# nixie_test.net
KiCad netlist of a schematic drawn in EAGLE
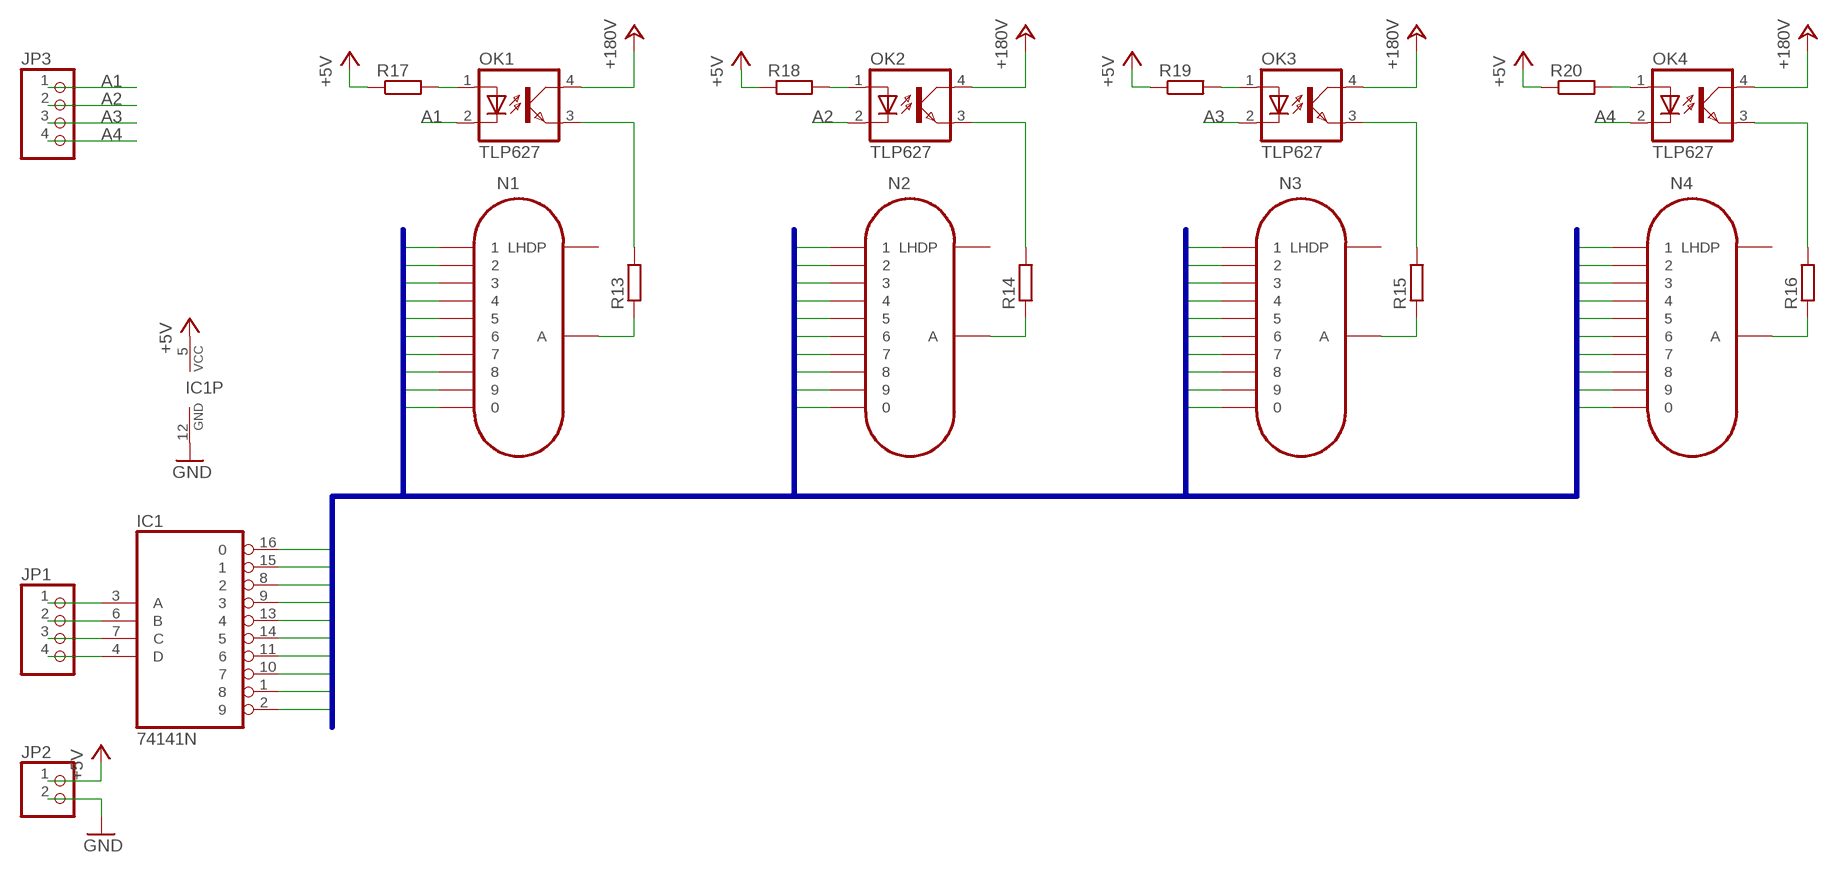
[diagram p0: schematic, sheet 1]

(export (version "E")
  (design (tool "Eeschema 10.0.6"))
  (components
    (comp (ref "IC1")
      (value "74141N")
      (footprint "eagle-import:DIL16")
      (libsource (lib "eagle-import") (part "74141N"))
    )
    (comp (ref "JP1")
      (value "PINHD-1X4")
      (footprint "eagle-import:1X04")
      (libsource (lib "eagle-import") (part "PINHD-1X4"))
    )
    (comp (ref "JP2")
      (value "PINHD-1X2")
      (footprint "eagle-import:1X02")
      (libsource (lib "eagle-import") (part "PINHD-1X2"))
    )
    (comp (ref "JP3")
      (value "PINHD-1X4")
      (footprint "eagle-import:1X04")
      (libsource (lib "eagle-import") (part "PINHD-1X4"))
    )
    (comp (ref "N1")
      (value "IN-12B")
      (footprint "eagle-import:IN-12")
      (libsource (lib "eagle-import") (part "IN-12B"))
    )
    (comp (ref "N2")
      (value "IN-12B")
      (footprint "eagle-import:IN-12")
      (libsource (lib "eagle-import") (part "IN-12B"))
    )
    (comp (ref "N3")
      (value "IN-12B")
      (footprint "eagle-import:IN-12")
      (libsource (lib "eagle-import") (part "IN-12B"))
    )
    (comp (ref "N4")
      (value "IN-12B")
      (footprint "eagle-import:IN-12")
      (libsource (lib "eagle-import") (part "IN-12B"))
    )
    (comp (ref "OK1")
      (value "TLP627")
      (footprint "eagle-import:4-SMD")
      (libsource (lib "eagle-import") (part "TLP627"))
    )
    (comp (ref "OK2")
      (value "TLP627")
      (footprint "eagle-import:4-SMD")
      (libsource (lib "eagle-import") (part "TLP627"))
    )
    (comp (ref "OK3")
      (value "TLP627")
      (footprint "eagle-import:4-SMD")
      (libsource (lib "eagle-import") (part "TLP627"))
    )
    (comp (ref "OK4")
      (value "TLP627")
      (footprint "eagle-import:4-SMD")
      (libsource (lib "eagle-import") (part "TLP627"))
    )
    (comp (ref "R13")
      (value "R-EU_10")
      (footprint "eagle-import:0207_10")
      (libsource (lib "eagle-import") (part "R-EU_10"))
    )
    (comp (ref "R14")
      (value "R-EU_10")
      (footprint "eagle-import:0207_10")
      (libsource (lib "eagle-import") (part "R-EU_10"))
    )
    (comp (ref "R15")
      (value "R-EU_10")
      (footprint "eagle-import:0207_10")
      (libsource (lib "eagle-import") (part "R-EU_10"))
    )
    (comp (ref "R16")
      (value "R-EU_10")
      (footprint "eagle-import:0207_10")
      (libsource (lib "eagle-import") (part "R-EU_10"))
    )
    (comp (ref "R17")
      (value "R-EU_10")
      (footprint "eagle-import:0207_10")
      (libsource (lib "eagle-import") (part "R-EU_10"))
    )
    (comp (ref "R18")
      (value "R-EU_10")
      (footprint "eagle-import:0207_10")
      (libsource (lib "eagle-import") (part "R-EU_10"))
    )
    (comp (ref "R19")
      (value "R-EU_10")
      (footprint "eagle-import:0207_10")
      (libsource (lib "eagle-import") (part "R-EU_10"))
    )
    (comp (ref "R20")
      (value "R-EU_10")
      (footprint "eagle-import:0207_10")
      (libsource (lib "eagle-import") (part "R-EU_10"))
    )
  )
  (nets
    (net (code "1") (name "+5V") (class "Default")
      (node (ref "IC1") (pin "5") (pinfunction "VCC_5") (pintype "power_in"))
      (node (ref "JP2") (pin "1") (pinfunction "1_1") (pintype "passive"))
      (node (ref "R17") (pin "1") (pinfunction "1_1") (pintype "passive"))
      (node (ref "R18") (pin "1") (pinfunction "1_1") (pintype "passive"))
      (node (ref "R19") (pin "1") (pinfunction "1_1") (pintype "passive"))
      (node (ref "R20") (pin "1") (pinfunction "1_1") (pintype "passive"))
    )
    (net (code "2") (name "+180V") (class "Default")
      (node (ref "OK1") (pin "4") (pinfunction "COL_4") (pintype "passive"))
      (node (ref "OK2") (pin "4") (pinfunction "COL_4") (pintype "passive"))
      (node (ref "OK3") (pin "4") (pinfunction "COL_4") (pintype "passive"))
      (node (ref "OK4") (pin "4") (pinfunction "COL_4") (pintype "passive"))
    )
    (net (code "3") (name "/A1") (class "Default")
      (node (ref "JP3") (pin "1") (pinfunction "1_1") (pintype "passive"))
      (node (ref "OK1") (pin "2") (pinfunction "C_2") (pintype "passive"))
    )
    (net (code "4") (name "/A2") (class "Default")
      (node (ref "JP3") (pin "2") (pinfunction "2_2") (pintype "passive"))
      (node (ref "OK2") (pin "2") (pinfunction "C_2") (pintype "passive"))
    )
    (net (code "5") (name "/A3") (class "Default")
      (node (ref "JP3") (pin "3") (pinfunction "3_3") (pintype "passive"))
      (node (ref "OK3") (pin "2") (pinfunction "C_2") (pintype "passive"))
    )
    (net (code "6") (name "/A4") (class "Default")
      (node (ref "JP3") (pin "4") (pinfunction "4_4") (pintype "passive"))
      (node (ref "OK4") (pin "2") (pinfunction "C_2") (pintype "passive"))
    )
    (net (code "7") (name "/C0") (class "Default")
      (node (ref "IC1") (pin "16") (pinfunction "0_16") (pintype "open_collector"))
      (node (ref "N1") (pin "0") (pinfunction "0_0") (pintype "bidirectional"))
      (node (ref "N2") (pin "0") (pinfunction "0_0") (pintype "bidirectional"))
      (node (ref "N3") (pin "0") (pinfunction "0_0") (pintype "bidirectional"))
      (node (ref "N4") (pin "0") (pinfunction "0_0") (pintype "bidirectional"))
    )
    (net (code "8") (name "/C1") (class "Default")
      (node (ref "IC1") (pin "15") (pinfunction "1_15") (pintype "open_collector"))
      (node (ref "N1") (pin "1") (pinfunction "1_1") (pintype "bidirectional"))
      (node (ref "N2") (pin "1") (pinfunction "1_1") (pintype "bidirectional"))
      (node (ref "N3") (pin "1") (pinfunction "1_1") (pintype "bidirectional"))
      (node (ref "N4") (pin "1") (pinfunction "1_1") (pintype "bidirectional"))
    )
    (net (code "9") (name "/C2") (class "Default")
      (node (ref "IC1") (pin "8") (pinfunction "2_8") (pintype "open_collector"))
      (node (ref "N1") (pin "2") (pinfunction "2_2") (pintype "bidirectional"))
      (node (ref "N2") (pin "2") (pinfunction "2_2") (pintype "bidirectional"))
      (node (ref "N3") (pin "2") (pinfunction "2_2") (pintype "bidirectional"))
      (node (ref "N4") (pin "2") (pinfunction "2_2") (pintype "bidirectional"))
    )
    (net (code "10") (name "/C3") (class "Default")
      (node (ref "IC1") (pin "9") (pinfunction "3_9") (pintype "open_collector"))
      (node (ref "N1") (pin "3") (pinfunction "3_3") (pintype "bidirectional"))
      (node (ref "N2") (pin "3") (pinfunction "3_3") (pintype "bidirectional"))
      (node (ref "N3") (pin "3") (pinfunction "3_3") (pintype "bidirectional"))
      (node (ref "N4") (pin "3") (pinfunction "3_3") (pintype "bidirectional"))
    )
    (net (code "11") (name "/C4") (class "Default")
      (node (ref "IC1") (pin "13") (pinfunction "4_13") (pintype "open_collector"))
      (node (ref "N1") (pin "4") (pinfunction "4_4") (pintype "bidirectional"))
      (node (ref "N2") (pin "4") (pinfunction "4_4") (pintype "bidirectional"))
      (node (ref "N3") (pin "4") (pinfunction "4_4") (pintype "bidirectional"))
      (node (ref "N4") (pin "4") (pinfunction "4_4") (pintype "bidirectional"))
    )
    (net (code "12") (name "/C5") (class "Default")
      (node (ref "IC1") (pin "14") (pinfunction "5_14") (pintype "open_collector"))
      (node (ref "N1") (pin "5") (pinfunction "5_5") (pintype "bidirectional"))
      (node (ref "N2") (pin "5") (pinfunction "5_5") (pintype "bidirectional"))
      (node (ref "N3") (pin "5") (pinfunction "5_5") (pintype "bidirectional"))
      (node (ref "N4") (pin "5") (pinfunction "5_5") (pintype "bidirectional"))
    )
    (net (code "13") (name "/C6") (class "Default")
      (node (ref "IC1") (pin "11") (pinfunction "6_11") (pintype "open_collector"))
      (node (ref "N1") (pin "6") (pinfunction "6_6") (pintype "bidirectional"))
      (node (ref "N2") (pin "6") (pinfunction "6_6") (pintype "bidirectional"))
      (node (ref "N3") (pin "6") (pinfunction "6_6") (pintype "bidirectional"))
      (node (ref "N4") (pin "6") (pinfunction "6_6") (pintype "bidirectional"))
    )
    (net (code "14") (name "/C7") (class "Default")
      (node (ref "IC1") (pin "10") (pinfunction "7_10") (pintype "open_collector"))
      (node (ref "N1") (pin "7") (pinfunction "7_7") (pintype "bidirectional"))
      (node (ref "N2") (pin "7") (pinfunction "7_7") (pintype "bidirectional"))
      (node (ref "N3") (pin "7") (pinfunction "7_7") (pintype "bidirectional"))
      (node (ref "N4") (pin "7") (pinfunction "7_7") (pintype "bidirectional"))
    )
    (net (code "15") (name "/C8") (class "Default")
      (node (ref "IC1") (pin "1") (pinfunction "8_1") (pintype "open_collector"))
      (node (ref "N1") (pin "8") (pinfunction "8_8") (pintype "bidirectional"))
      (node (ref "N2") (pin "8") (pinfunction "8_8") (pintype "bidirectional"))
      (node (ref "N3") (pin "8") (pinfunction "8_8") (pintype "bidirectional"))
      (node (ref "N4") (pin "8") (pinfunction "8_8") (pintype "bidirectional"))
    )
    (net (code "16") (name "/C9") (class "Default")
      (node (ref "IC1") (pin "2") (pinfunction "9_2") (pintype "open_collector"))
      (node (ref "N1") (pin "9") (pinfunction "9_9") (pintype "bidirectional"))
      (node (ref "N2") (pin "9") (pinfunction "9_9") (pintype "bidirectional"))
      (node (ref "N3") (pin "9") (pinfunction "9_9") (pintype "bidirectional"))
      (node (ref "N4") (pin "9") (pinfunction "9_9") (pintype "bidirectional"))
    )
    (net (code "17") (name "GND") (class "Default")
      (node (ref "IC1") (pin "12") (pinfunction "GND_12") (pintype "power_in"))
      (node (ref "JP2") (pin "2") (pinfunction "2_2") (pintype "passive"))
    )
    (net (code "18") (name "Net-(IC1A-A)") (class "Default")
      (node (ref "IC1") (pin "3") (pinfunction "A_3") (pintype "input"))
      (node (ref "JP1") (pin "1") (pinfunction "1_1") (pintype "passive"))
    )
    (net (code "19") (name "Net-(IC1A-B)") (class "Default")
      (node (ref "IC1") (pin "6") (pinfunction "B_6") (pintype "input"))
      (node (ref "JP1") (pin "2") (pinfunction "2_2") (pintype "passive"))
    )
    (net (code "20") (name "Net-(IC1A-C)") (class "Default")
      (node (ref "IC1") (pin "7") (pinfunction "C_7") (pintype "input"))
      (node (ref "JP1") (pin "3") (pinfunction "3_3") (pintype "passive"))
    )
    (net (code "21") (name "Net-(IC1A-D)") (class "Default")
      (node (ref "IC1") (pin "4") (pinfunction "D_4") (pintype "input"))
      (node (ref "JP1") (pin "4") (pinfunction "4_4") (pintype "passive"))
    )
    (net (code "22") (name "Net-(N1-PadA)") (class "Default")
      (node (ref "N1") (pin "A") (pinfunction "A_A") (pintype "bidirectional"))
      (node (ref "R13") (pin "1") (pinfunction "1_1") (pintype "passive"))
    )
    (net (code "23") (name "Net-(N2-PadA)") (class "Default")
      (node (ref "N2") (pin "A") (pinfunction "A_A") (pintype "bidirectional"))
      (node (ref "R14") (pin "1") (pinfunction "1_1") (pintype "passive"))
    )
    (net (code "24") (name "Net-(N3-PadA)") (class "Default")
      (node (ref "N3") (pin "A") (pinfunction "A_A") (pintype "bidirectional"))
      (node (ref "R15") (pin "1") (pinfunction "1_1") (pintype "passive"))
    )
    (net (code "25") (name "Net-(N4-PadA)") (class "Default")
      (node (ref "N4") (pin "A") (pinfunction "A_A") (pintype "bidirectional"))
      (node (ref "R16") (pin "1") (pinfunction "1_1") (pintype "passive"))
    )
    (net (code "26") (name "Net-(OK1-A)") (class "Default")
      (node (ref "OK1") (pin "1") (pinfunction "A_1") (pintype "passive"))
      (node (ref "R17") (pin "2") (pinfunction "2_2") (pintype "passive"))
    )
    (net (code "27") (name "Net-(OK1-EMIT)") (class "Default")
      (node (ref "OK1") (pin "3") (pinfunction "EMIT_3") (pintype "passive"))
      (node (ref "R13") (pin "2") (pinfunction "2_2") (pintype "passive"))
    )
    (net (code "28") (name "Net-(OK2-A)") (class "Default")
      (node (ref "OK2") (pin "1") (pinfunction "A_1") (pintype "passive"))
      (node (ref "R18") (pin "2") (pinfunction "2_2") (pintype "passive"))
    )
    (net (code "29") (name "Net-(OK2-EMIT)") (class "Default")
      (node (ref "OK2") (pin "3") (pinfunction "EMIT_3") (pintype "passive"))
      (node (ref "R14") (pin "2") (pinfunction "2_2") (pintype "passive"))
    )
    (net (code "30") (name "Net-(OK3-A)") (class "Default")
      (node (ref "OK3") (pin "1") (pinfunction "A_1") (pintype "passive"))
      (node (ref "R19") (pin "2") (pinfunction "2_2") (pintype "passive"))
    )
    (net (code "31") (name "Net-(OK3-EMIT)") (class "Default")
      (node (ref "OK3") (pin "3") (pinfunction "EMIT_3") (pintype "passive"))
      (node (ref "R15") (pin "2") (pinfunction "2_2") (pintype "passive"))
    )
    (net (code "32") (name "Net-(OK4-A)") (class "Default")
      (node (ref "OK4") (pin "1") (pinfunction "A_1") (pintype "passive"))
      (node (ref "R20") (pin "2") (pinfunction "2_2") (pintype "passive"))
    )
    (net (code "33") (name "Net-(OK4-EMIT)") (class "Default")
      (node (ref "OK4") (pin "3") (pinfunction "EMIT_3") (pintype "passive"))
      (node (ref "R16") (pin "2") (pinfunction "2_2") (pintype "passive"))
    )
    (net (code "34") (name "unconnected-(N1-PadLHDP)") (class "Default")
      (node (ref "N1") (pin "LHDP") (pinfunction "LHDP_LHDP") (pintype "bidirectional"))
    )
    (net (code "35") (name "unconnected-(N2-PadLHDP)") (class "Default")
      (node (ref "N2") (pin "LHDP") (pinfunction "LHDP_LHDP") (pintype "bidirectional"))
    )
    (net (code "36") (name "unconnected-(N3-PadLHDP)") (class "Default")
      (node (ref "N3") (pin "LHDP") (pinfunction "LHDP_LHDP") (pintype "bidirectional"))
    )
    (net (code "37") (name "unconnected-(N4-PadLHDP)") (class "Default")
      (node (ref "N4") (pin "LHDP") (pinfunction "LHDP_LHDP") (pintype "bidirectional"))
    )
  )
)
